# KEY.net
KiCad netlist of a schematic drawn in Altium Designer
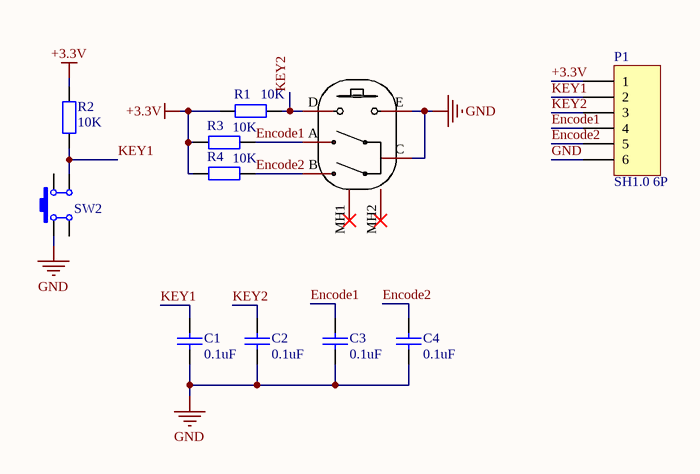
[diagram p0: KEY.SchDoc]

(export (version "E")
  (design (tool "Eeschema 10.0.6"))
  (components
    (comp (ref "C1")
      (value "0.1uF")
      (footprint "C0603_L")
      (description "贴片电容")
      (libsource (lib "0.1 - 电阻-电容-电感-磁珠-电位器") (part "C"))
    )
    (comp (ref "C2")
      (value "0.1uF")
      (footprint "C0603_L")
      (description "贴片电容")
      (libsource (lib "0.1 - 电阻-电容-电感-磁珠-电位器") (part "C"))
    )
    (comp (ref "C3")
      (value "0.1uF")
      (footprint "C0603_L")
      (description "贴片电容")
      (libsource (lib "0.1 - 电阻-电容-电感-磁珠-电位器") (part "C"))
    )
    (comp (ref "C4")
      (value "0.1uF")
      (footprint "C0603_L")
      (description "贴片电容")
      (libsource (lib "0.1 - 电阻-电容-电感-磁珠-电位器") (part "C"))
    )
    (comp (ref "P1")
      (value "SH1.0 6P")
      (footprint "SH 1.0-WS-6P")
      (description "Header, 6-Pin")
      (fields (field (name "PUBLISHER") "Altium Limited"))
      (libsource (lib "Miscellaneous Connectors") (part "Header 6"))
    )
    (comp (ref "R1")
      (value "10K")
      (footprint "R0603_L")
      (description "贴片电阻")
      (libsource (lib "0.1 - 电阻-电容-电感-磁珠-电位器") (part "R"))
    )
    (comp (ref "R2")
      (value "10K")
      (footprint "R0603_L")
      (description "贴片电阻")
      (libsource (lib "0.1 - 电阻-电容-电感-磁珠-电位器") (part "R"))
    )
    (comp (ref "R3")
      (value "10K")
      (footprint "R0603_L")
      (description "贴片电阻")
      (libsource (lib "0.1 - 电阻-电容-电感-磁珠-电位器") (part "R"))
    )
    (comp (ref "R4")
      (value "10K")
      (footprint "R0603_L")
      (description "贴片电阻")
      (libsource (lib "0.1 - 电阻-电容-电感-磁珠-电位器") (part "R"))
    )
    (comp (ref "SW1")
      (value "EC11K1524406")
      (footprint "SW-TH_EC11K1524406 - duplicate")
      (fields (field (name "MANUFACTURER") "ALPSALPINE(阿尔卑斯阿尔派)"))
      (libsource (lib "altium-import") (part "root_0_EC11K1524406_"))
    )
    (comp (ref "SW2")
      (value "12x12x5")
      (footprint "SW DIP-12*12*4.3")
      (description "直插12x12轻触开关")
      (libsource (lib "0.7 - 常用按键-开关-蜂鸣器-电池-测试点") (part "TSW DIP-12x12"))
    )
  )
  (nets
    (net (code "1") (name "+3.3V") (class "Default")
      (node (ref "P1") (pin "1") (pinfunction "1_1") (pintype "passive"))
      (node (ref "R1") (pin "2") (pinfunction "2_2") (pintype "passive"))
      (node (ref "R2") (pin "2") (pinfunction "2_2") (pintype "passive"))
      (node (ref "R3") (pin "2") (pinfunction "2_2") (pintype "passive"))
      (node (ref "R4") (pin "2") (pinfunction "2_2") (pintype "passive"))
    )
    (net (code "2") (name "/Encode1") (class "Default")
      (node (ref "C3") (pin "1") (pinfunction "1_1") (pintype "passive"))
      (node (ref "P1") (pin "4") (pinfunction "4_4") (pintype "passive"))
      (node (ref "R3") (pin "1") (pinfunction "1_1") (pintype "passive"))
      (node (ref "SW1") (pin "A") (pinfunction "A_A") (pintype "passive"))
    )
    (net (code "3") (name "/Encode2") (class "Default")
      (node (ref "C4") (pin "1") (pinfunction "1_1") (pintype "passive"))
      (node (ref "P1") (pin "5") (pinfunction "5_5") (pintype "passive"))
      (node (ref "R4") (pin "1") (pinfunction "1_1") (pintype "passive"))
      (node (ref "SW1") (pin "B") (pinfunction "B_B") (pintype "passive"))
    )
    (net (code "4") (name "/KEY1") (class "Default")
      (node (ref "C1") (pin "1") (pinfunction "1_1") (pintype "passive"))
      (node (ref "P1") (pin "2") (pinfunction "2_2") (pintype "passive"))
      (node (ref "R2") (pin "1") (pinfunction "1_1") (pintype "passive"))
      (node (ref "SW2") (pin "3") (pinfunction "3_3") (pintype "passive"))
    )
    (net (code "5") (name "/KEY2") (class "Default")
      (node (ref "C2") (pin "1") (pinfunction "1_1") (pintype "passive"))
      (node (ref "P1") (pin "3") (pinfunction "3_3") (pintype "passive"))
      (node (ref "R1") (pin "1") (pinfunction "1_1") (pintype "passive"))
      (node (ref "SW1") (pin "D") (pinfunction "D_D") (pintype "passive"))
    )
    (net (code "6") (name "GND") (class "Default")
      (node (ref "C1") (pin "2") (pinfunction "2_2") (pintype "passive"))
      (node (ref "C2") (pin "2") (pinfunction "2_2") (pintype "passive"))
      (node (ref "C3") (pin "2") (pinfunction "2_2") (pintype "passive"))
      (node (ref "C4") (pin "2") (pinfunction "2_2") (pintype "passive"))
      (node (ref "P1") (pin "6") (pinfunction "6_6") (pintype "passive"))
      (node (ref "SW1") (pin "C") (pinfunction "C_C") (pintype "passive"))
      (node (ref "SW1") (pin "E") (pinfunction "E_E") (pintype "passive"))
      (node (ref "SW2") (pin "1") (pinfunction "1_1") (pintype "passive"))
    )
    (net (code "7") (name "unconnected-(SW1-PadMH1)") (class "Default")
      (node (ref "SW1") (pin "MH1") (pinfunction "MH1_MH1") (pintype "passive+no_connect"))
    )
    (net (code "8") (name "unconnected-(SW1-PadMH2)") (class "Default")
      (node (ref "SW1") (pin "MH2") (pinfunction "MH2_MH2") (pintype "passive+no_connect"))
    )
    (net (code "9") (name "unconnected-(SW2-Pad2)") (class "Default")
      (node (ref "SW2") (pin "2") (pinfunction "2_2") (pintype "passive"))
    )
    (net (code "10") (name "unconnected-(SW2-Pad4)") (class "Default")
      (node (ref "SW2") (pin "4") (pinfunction "4_4") (pintype "passive"))
    )
  )
)
